# BOARD_CONN_805_24PIN.net
KiCad netlist of a schematic drawn in Altium Designer
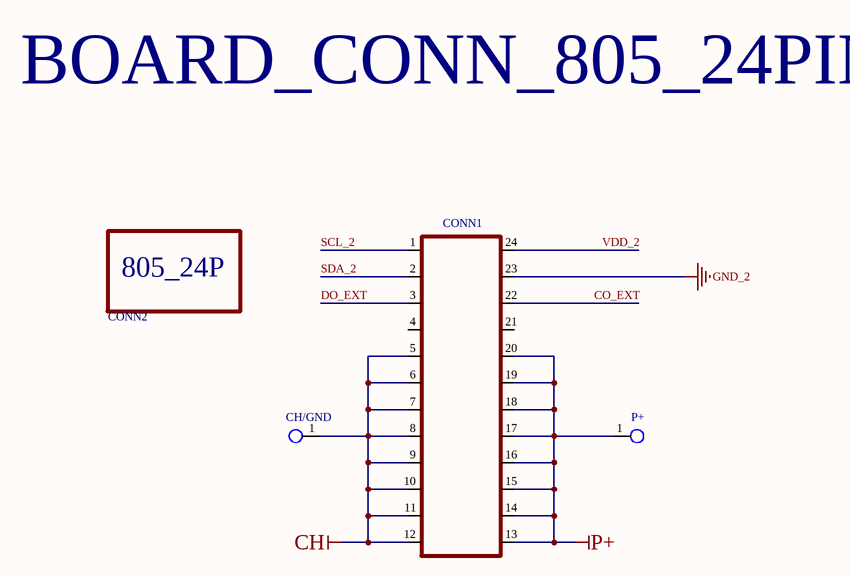
[diagram p0: BOARD_CONN_805_24PIN.SchDoc]

(export (version "E")
  (design (tool "Eeschema 10.0.6"))
  (components
    (comp (ref "CH/GND")
      (value "Test_Point_PCB")
      (footprint "Test_Point")
      (description "Test_Point")
      (libsource (lib "TEST_POINT") (part "TP_PCB?"))
    )
    (comp (ref "CONN1")
      (value "CONN_805_24P")
      (footprint "CONN_805_24P")
      (libsource (lib "CONN_805_24P") (part "CONN_805_24P"))
    )
    (comp (ref "CONN2") (value "805_24P") (footprint "805_24P") (libsource (lib "805_24P") (part "805_24P")))
    (comp (ref "P+")
      (value "Test_Point_PCB")
      (footprint "Test_Point")
      (description "Test_Point")
      (libsource (lib "TEST_POINT") (part "TP_PCB?"))
    )
  )
  (nets
    (net (code "1") (name "/CO_EXT") (class "Default") (node (ref "CONN1") (pin "22") (pintype "passive")))
    (net (code "2") (name "/DO_EXT") (class "Default") (node (ref "CONN1") (pin "3") (pintype "passive")))
    (net (code "3") (name "/SCL_2") (class "Default") (node (ref "CONN1") (pin "1") (pintype "passive")))
    (net (code "4") (name "/SDA_2") (class "Default") (node (ref "CONN1") (pin "2") (pintype "passive")))
    (net (code "5") (name "/VDD_2") (class "Default") (node (ref "CONN1") (pin "24") (pintype "passive")))
    (net (code "6") (name "CH") (class "Default")
      (node (ref "CH/GND") (pin "1") (pinfunction "G9_1") (pintype "passive"))
      (node (ref "CONN1") (pin "10") (pintype "passive"))
      (node (ref "CONN1") (pin "11") (pintype "passive"))
      (node (ref "CONN1") (pin "12") (pintype "passive"))
      (node (ref "CONN1") (pin "5") (pintype "passive"))
      (node (ref "CONN1") (pin "6") (pintype "passive"))
      (node (ref "CONN1") (pin "7") (pintype "passive"))
      (node (ref "CONN1") (pin "8") (pintype "passive"))
      (node (ref "CONN1") (pin "9") (pintype "passive"))
    )
    (net (code "7") (name "GND_2") (class "Default") (node (ref "CONN1") (pin "23") (pintype "passive")))
    (net (code "8") (name "P+") (class "Default")
      (node (ref "CONN1") (pin "13") (pintype "passive"))
      (node (ref "CONN1") (pin "14") (pintype "passive"))
      (node (ref "CONN1") (pin "15") (pintype "passive"))
      (node (ref "CONN1") (pin "16") (pintype "passive"))
      (node (ref "CONN1") (pin "17") (pintype "passive"))
      (node (ref "CONN1") (pin "18") (pintype "passive"))
      (node (ref "CONN1") (pin "19") (pintype "passive"))
      (node (ref "CONN1") (pin "20") (pintype "passive"))
      (node (ref "P+") (pin "1") (pinfunction "G9_1") (pintype "passive"))
    )
    (net (code "9") (name "unconnected-(CONN1-Pad4)") (class "Default")
      (node (ref "CONN1") (pin "4") (pintype "passive"))
    )
    (net (code "10") (name "unconnected-(CONN1-Pad21)") (class "Default")
      (node (ref "CONN1") (pin "21") (pintype "passive"))
    )
  )
)
